# mbed_6LoWPAN_Border_Router_HAT.net
KiCad netlist of a schematic drawn in EAGLE
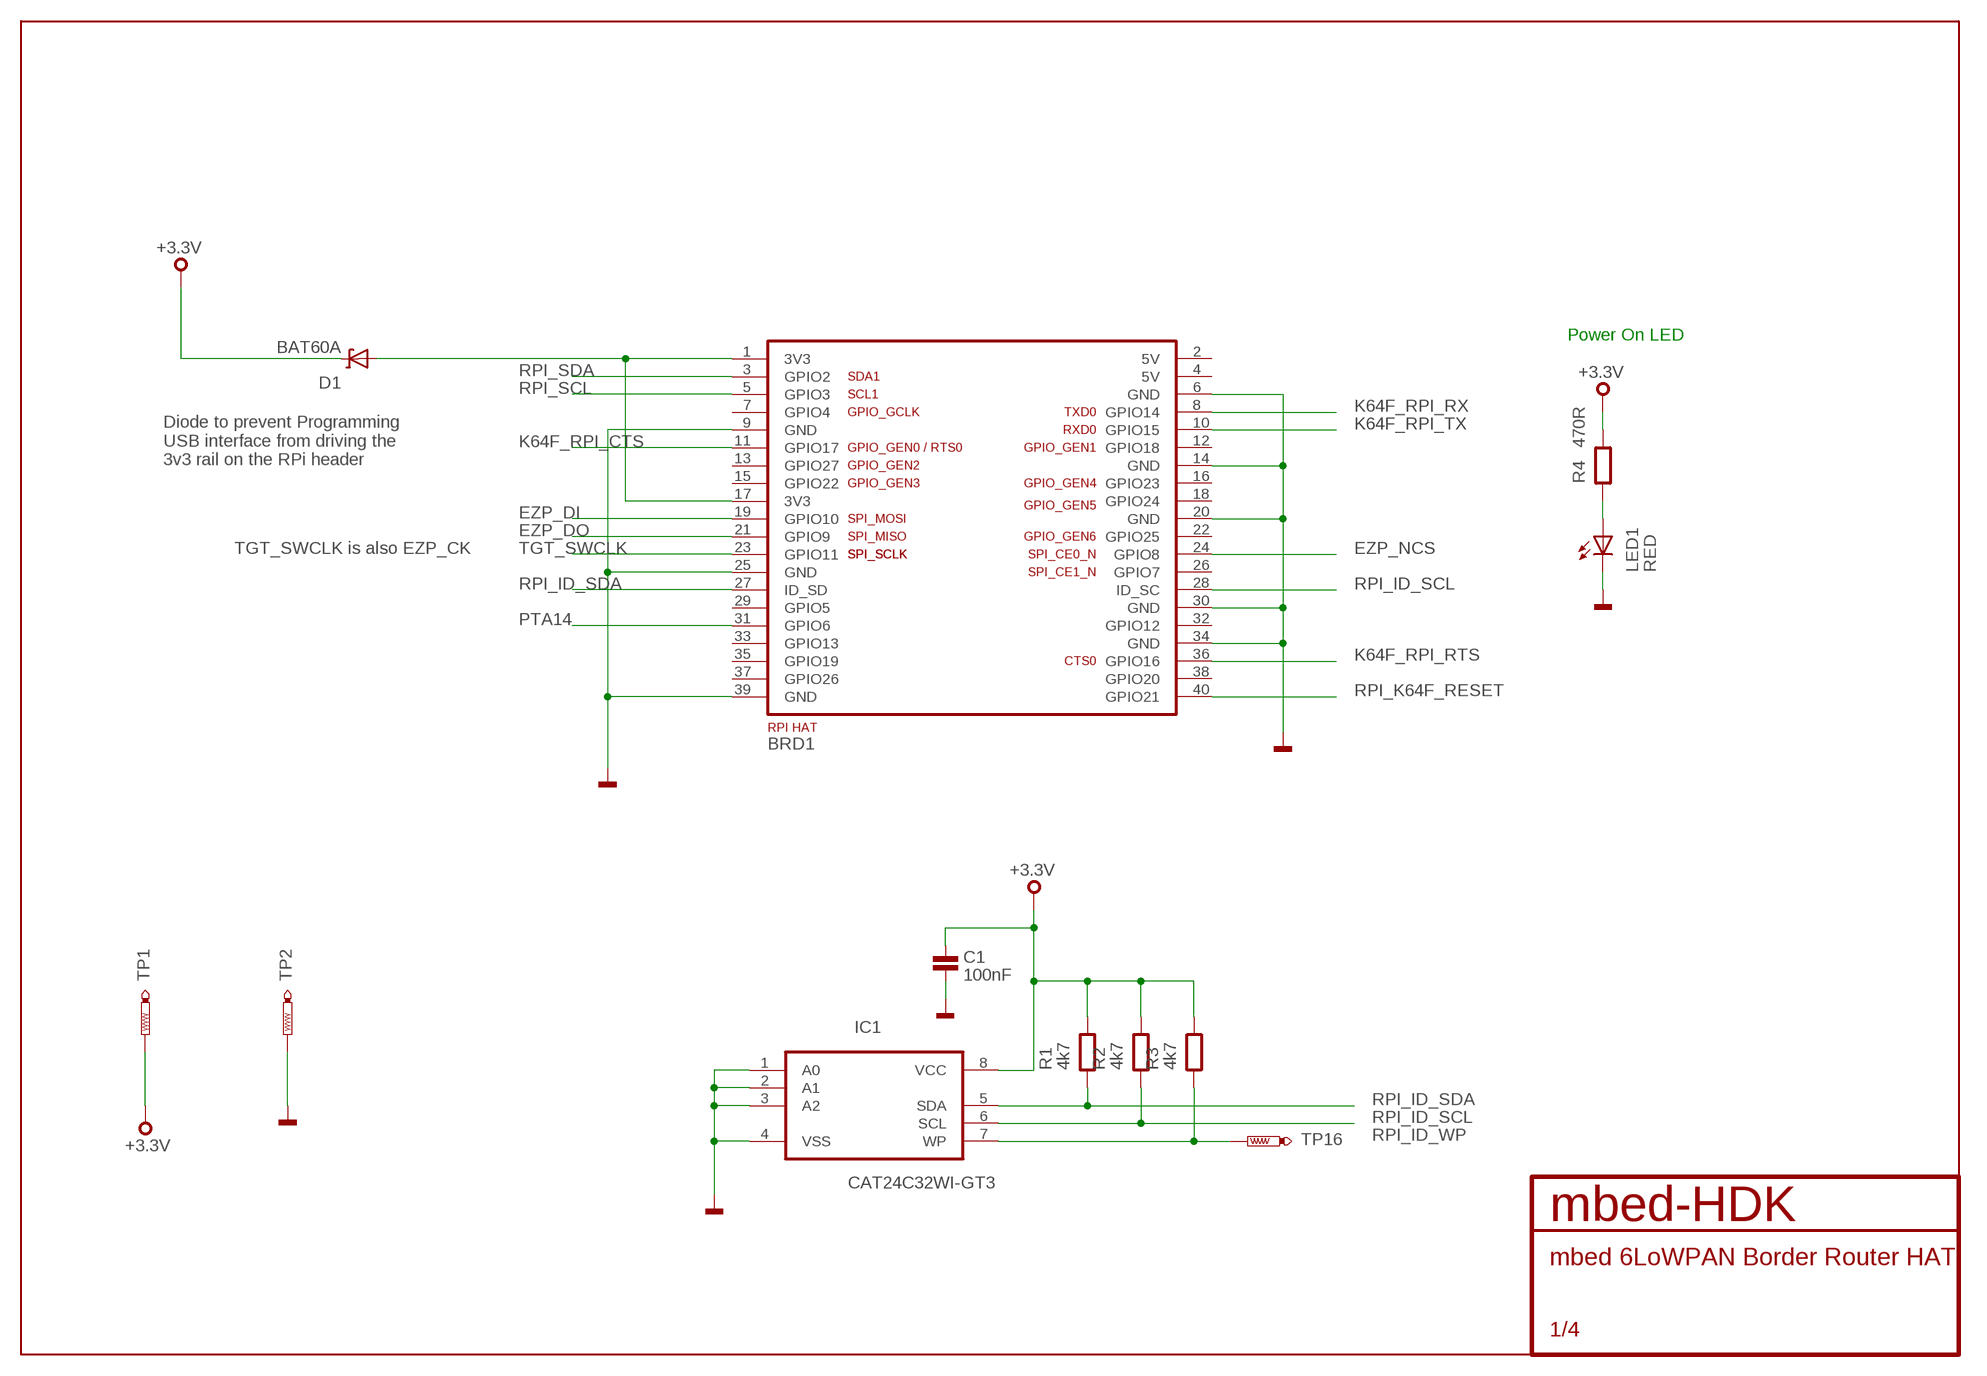
[diagram p0: schematic, sheet 1]
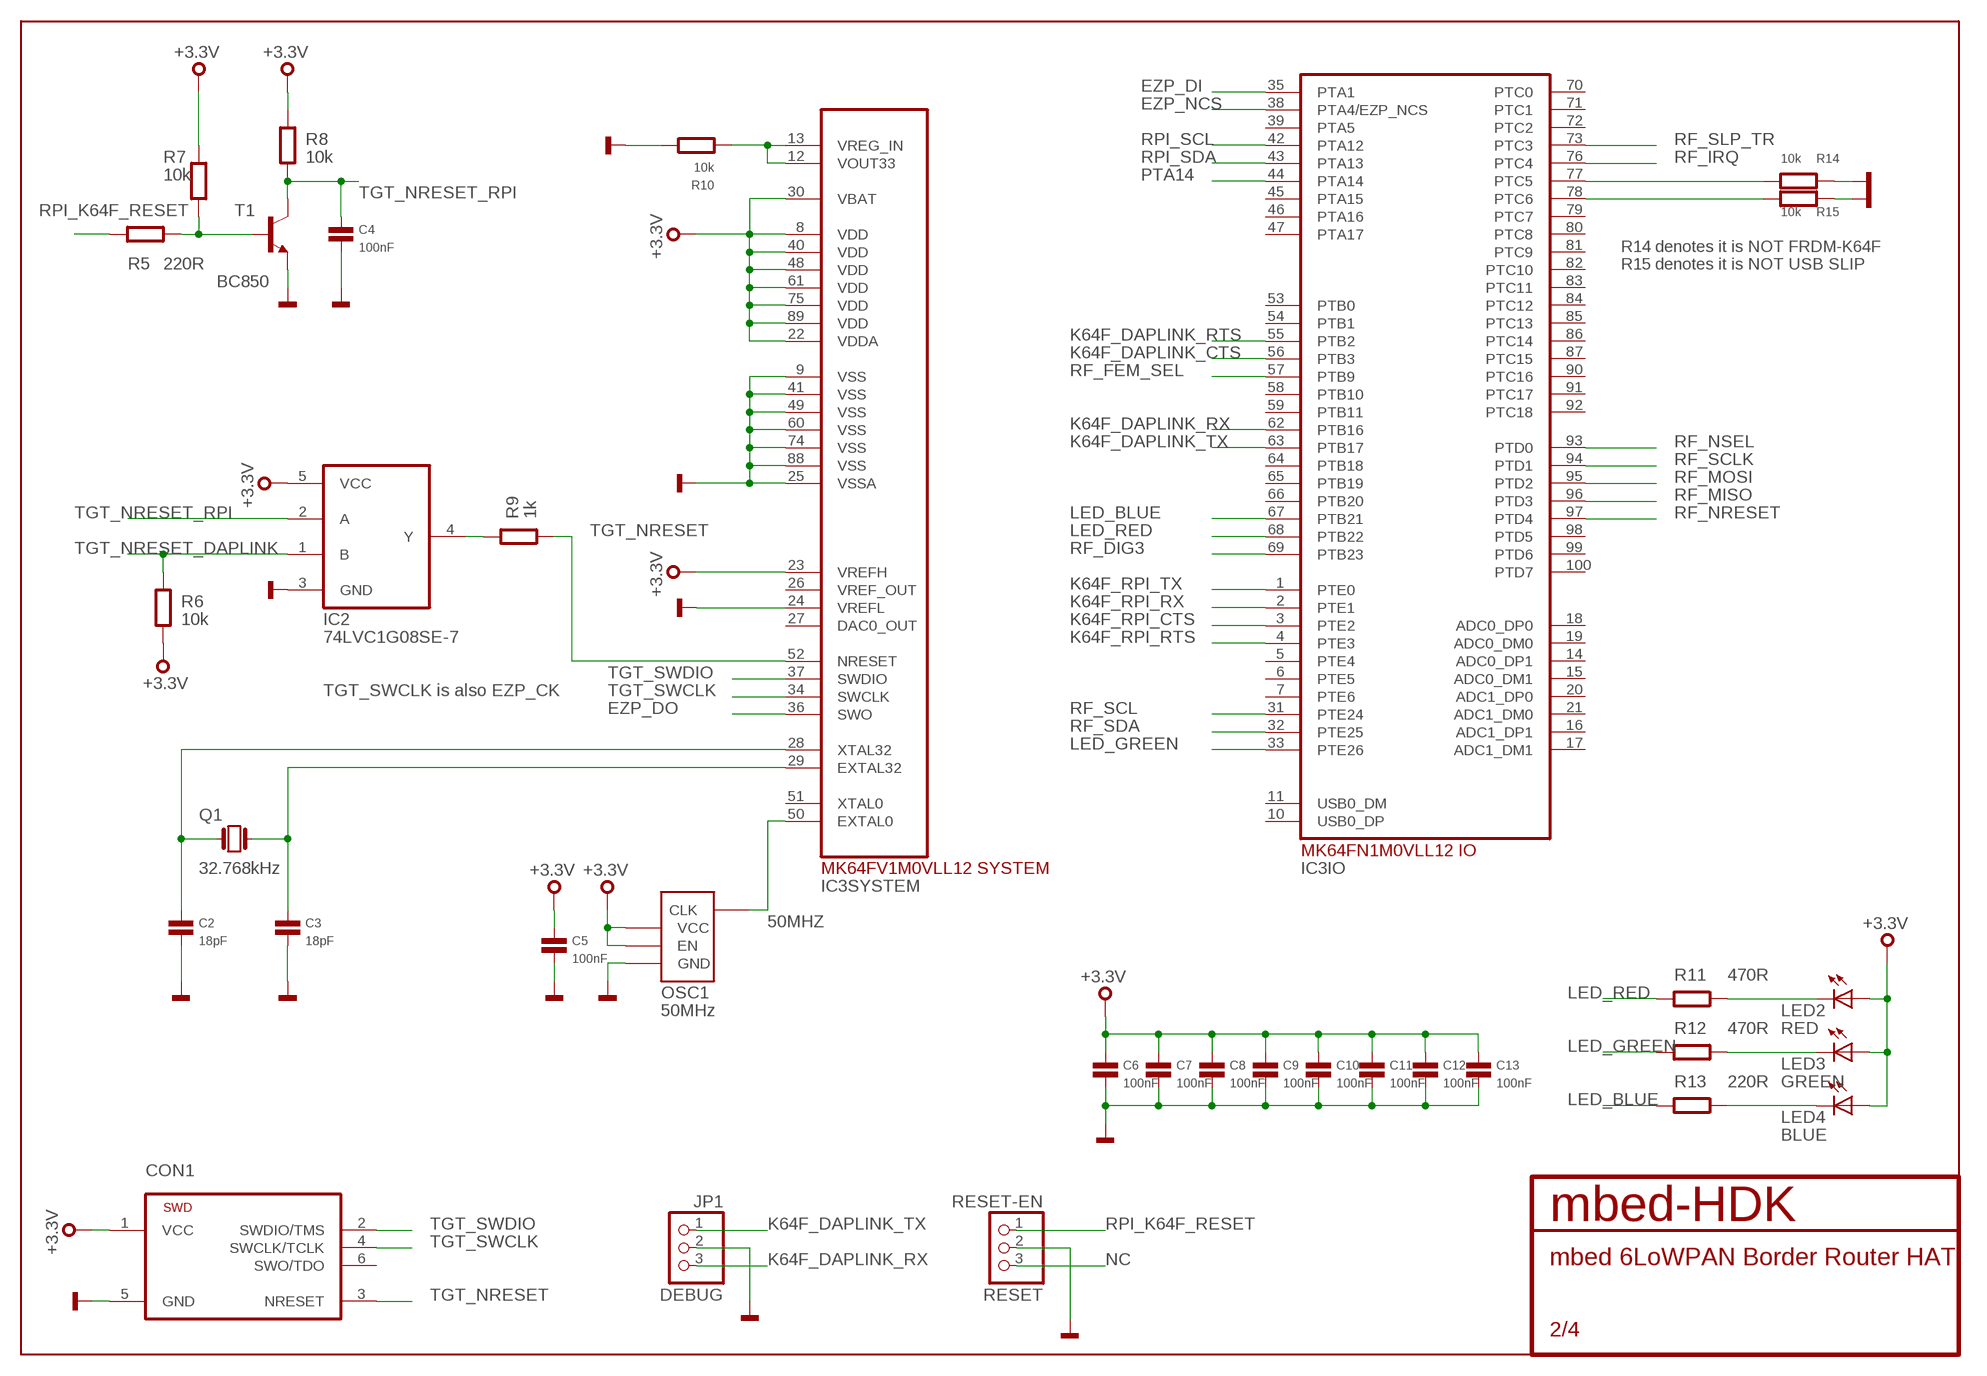
[diagram p1: schematic, sheet 2]
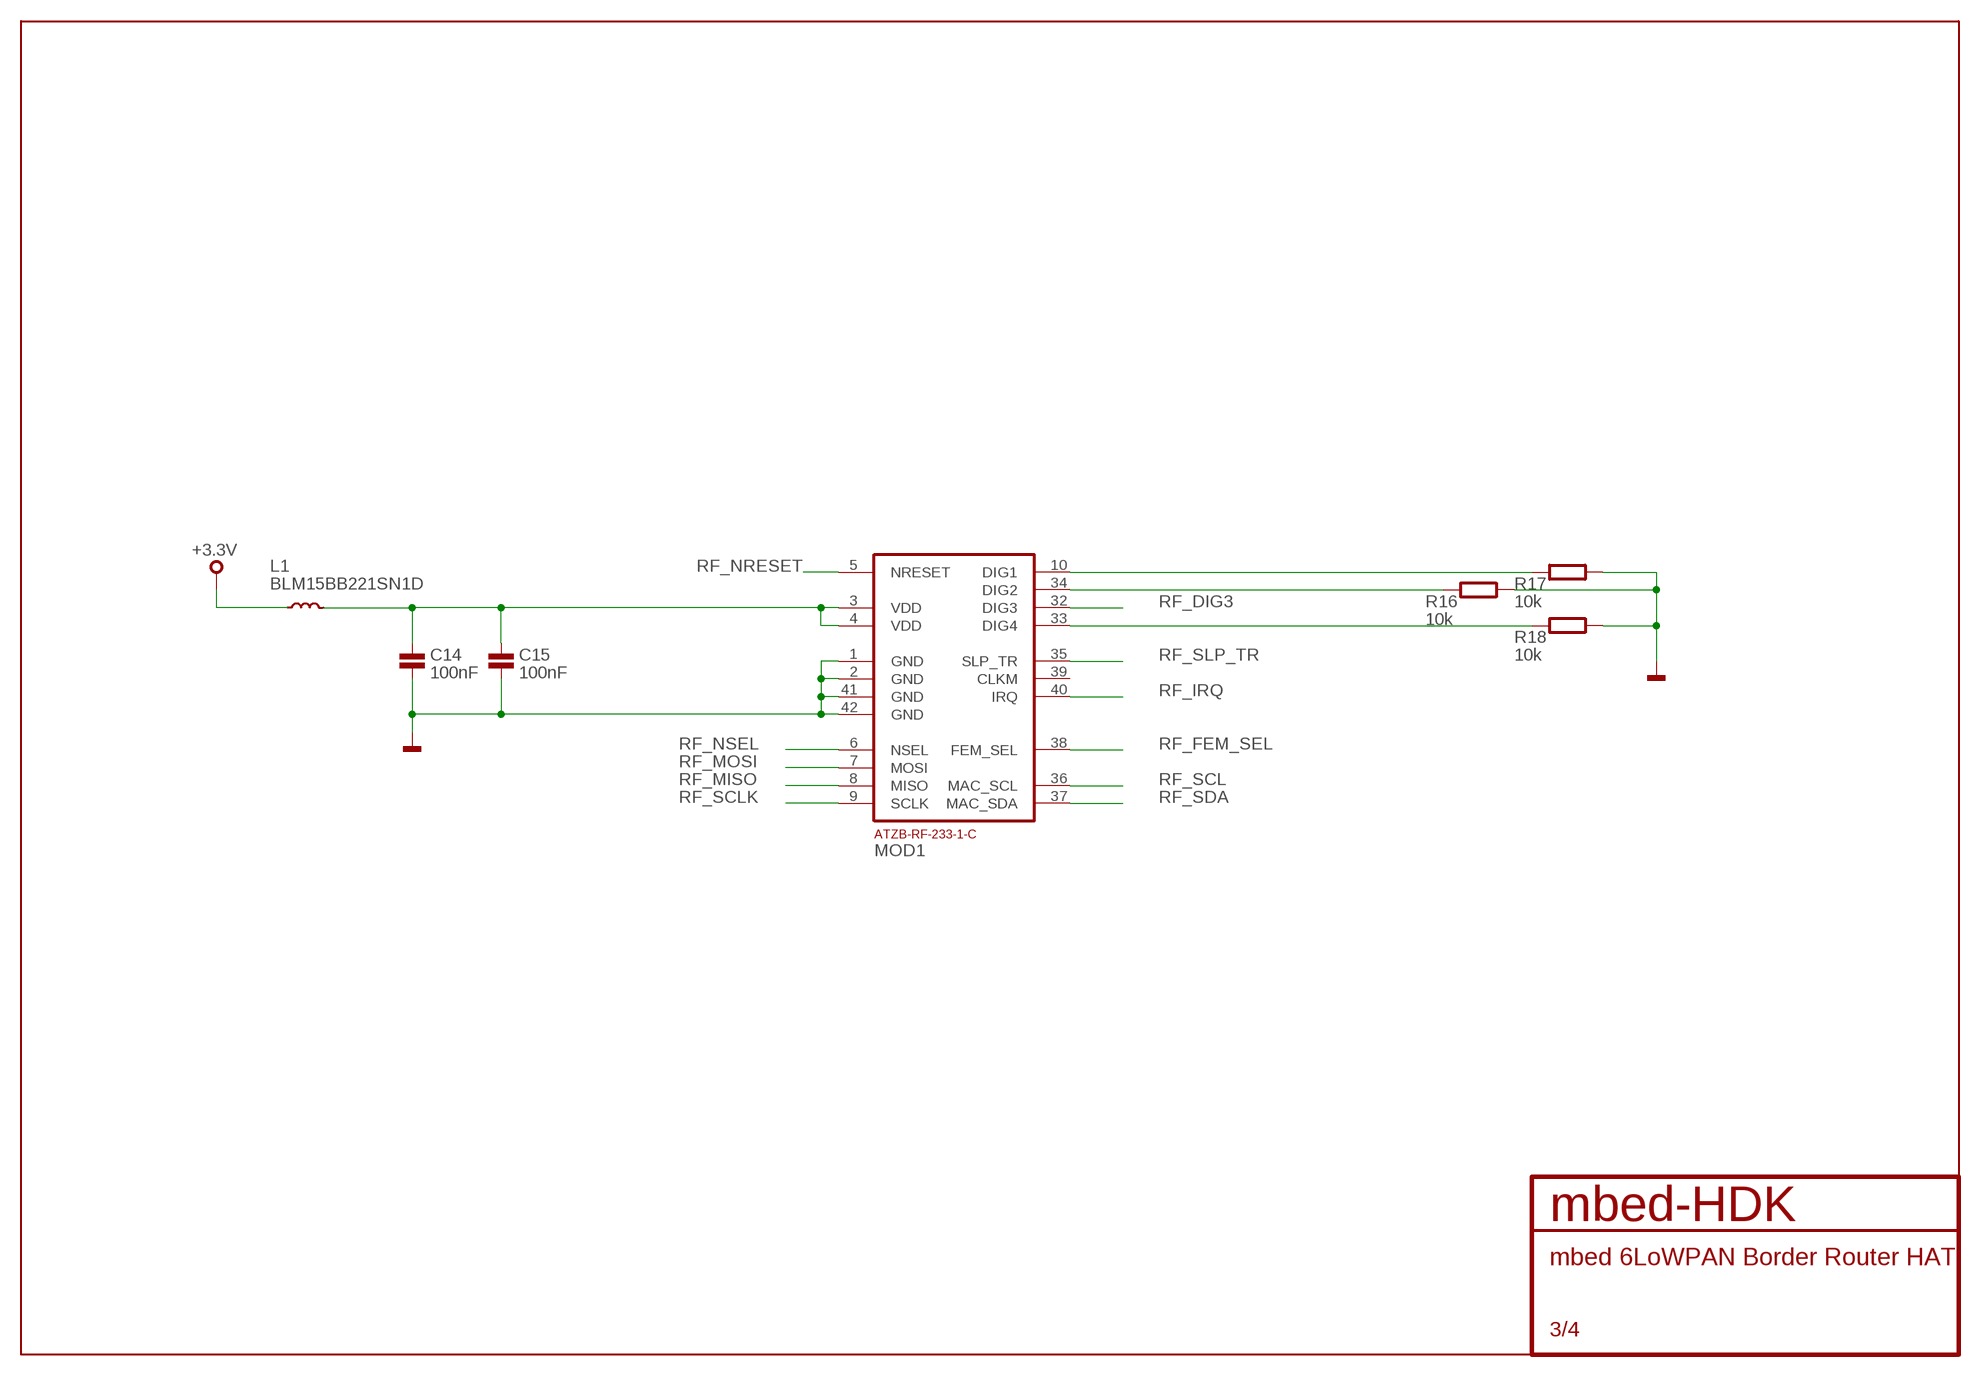
[diagram p2: schematic, sheet 3]
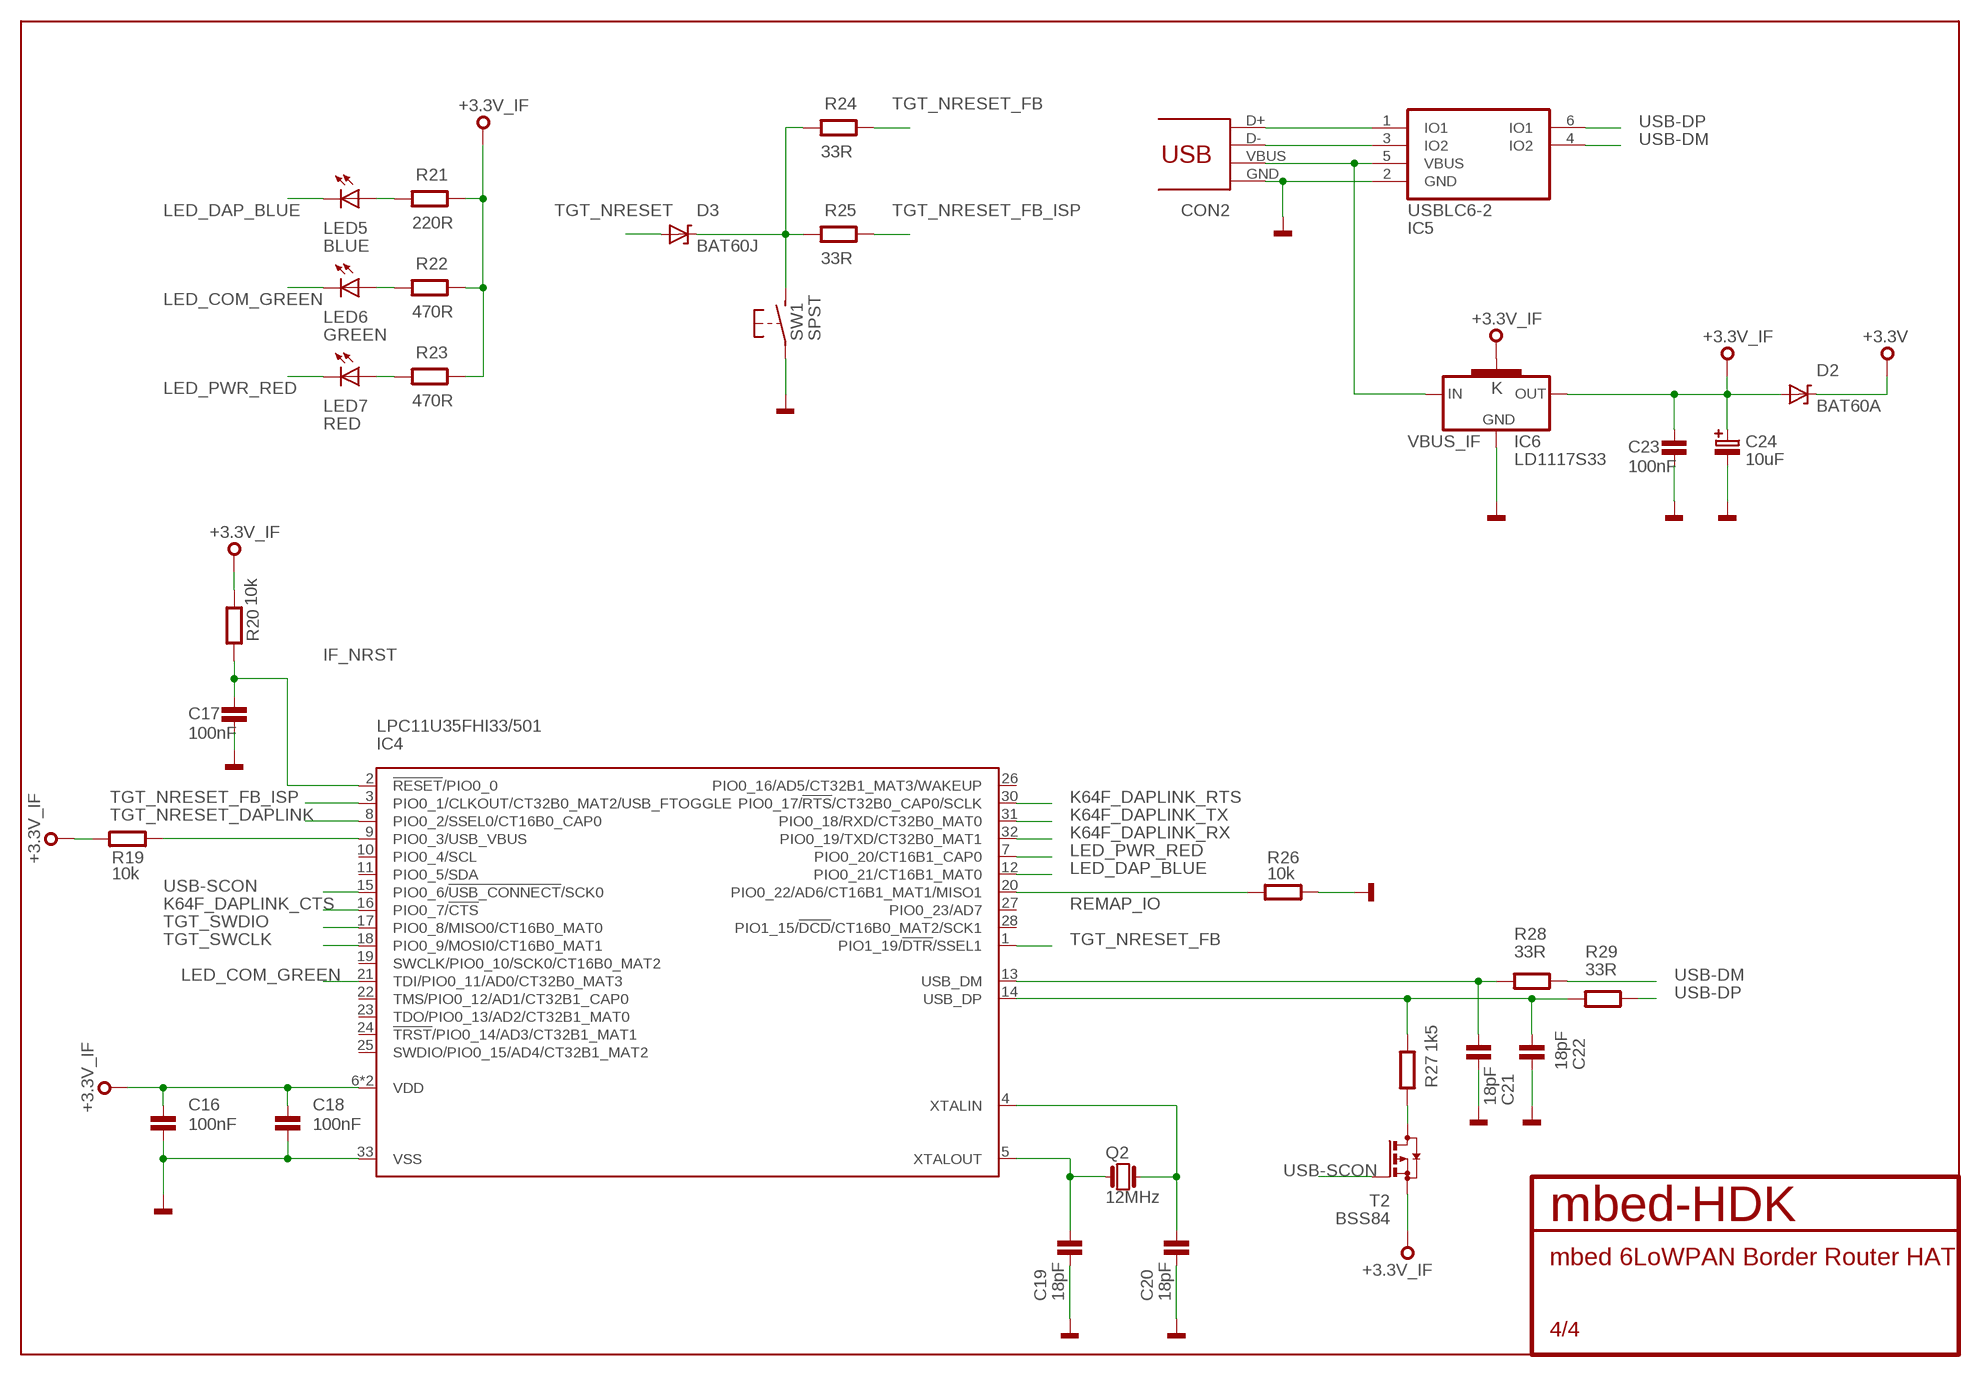
[diagram p3: schematic, sheet 4]

(export (version "E")
  (design (tool "Eeschema 10.0.6"))
  (components
    (comp (ref "C2")
      (value "18pF")
      (footprint "eagle-import:0402")
      (libsource (lib "eagle-import") (part "C0402"))
    )
    (comp (ref "C3")
      (value "18pF")
      (footprint "eagle-import:0402")
      (libsource (lib "eagle-import") (part "C0402"))
    )
    (comp (ref "C4")
      (value "100nF")
      (footprint "eagle-import:0402")
      (libsource (lib "eagle-import") (part "C0402"))
    )
    (comp (ref "C5")
      (value "100nF")
      (footprint "eagle-import:0402")
      (libsource (lib "eagle-import") (part "C0402"))
    )
    (comp (ref "C6")
      (value "100nF")
      (footprint "eagle-import:0402")
      (libsource (lib "eagle-import") (part "C0402"))
    )
    (comp (ref "C7")
      (value "100nF")
      (footprint "eagle-import:0402")
      (libsource (lib "eagle-import") (part "C0402"))
    )
    (comp (ref "C8")
      (value "100nF")
      (footprint "eagle-import:0402")
      (libsource (lib "eagle-import") (part "C0402"))
    )
    (comp (ref "C9")
      (value "100nF")
      (footprint "eagle-import:0402")
      (libsource (lib "eagle-import") (part "C0402"))
    )
    (comp (ref "C10")
      (value "100nF")
      (footprint "eagle-import:0402")
      (libsource (lib "eagle-import") (part "C0402"))
    )
    (comp (ref "C11")
      (value "100nF")
      (footprint "eagle-import:0402")
      (libsource (lib "eagle-import") (part "C0402"))
    )
    (comp (ref "C12")
      (value "100nF")
      (footprint "eagle-import:0402")
      (libsource (lib "eagle-import") (part "C0402"))
    )
    (comp (ref "C13")
      (value "100nF")
      (footprint "eagle-import:0402")
      (libsource (lib "eagle-import") (part "C0402"))
    )
    (comp (ref "CON1")
      (value "TC2030-CTX-NL")
      (footprint "eagle-import:TC2030-CTX-NL")
      (libsource (lib "eagle-import") (part "TC2030-CTX-NL"))
    )
    (comp (ref "IC2")
      (value "74LVC1G08SE-7")
      (footprint "eagle-import:SOT353")
      (libsource (lib "eagle-import") (part "74LVC1GXX"))
    )
    (comp (ref "IC3")
      (value "MK64FN1M0VLL12")
      (footprint "eagle-import:LQFP100")
      (libsource (lib "eagle-import") (part "MK64FN1M0VLL12"))
    )
    (comp (ref "JP1")
      (value "DEBUG")
      (footprint "eagle-import:1X03")
      (libsource (lib "eagle-import") (part "PINHD-1X3"))
    )
    (comp (ref "LED2")
      (value "RED")
      (footprint "eagle-import:CHIPLED_0603")
      (libsource (lib "eagle-import") (part "LED0603"))
    )
    (comp (ref "LED3")
      (value "GREEN")
      (footprint "eagle-import:CHIPLED_0603")
      (libsource (lib "eagle-import") (part "LED0603"))
    )
    (comp (ref "LED4")
      (value "BLUE")
      (footprint "eagle-import:CHIPLED_0603")
      (libsource (lib "eagle-import") (part "LED0603"))
    )
    (comp (ref "OSC1")
      (value "50MHz")
      (footprint "eagle-import:3.2X.2.5")
      (libsource (lib "eagle-import") (part "OSCILLATOR3.2X2.5"))
    )
    (comp (ref "Q1")
      (value "32.768kHz")
      (footprint "eagle-import:FC135")
      (libsource (lib "eagle-import") (part "Q_FC135"))
    )
    (comp (ref "R5")
      (value "220R")
      (footprint "eagle-import:0402")
      (libsource (lib "eagle-import") (part "R0402"))
    )
    (comp (ref "R6")
      (value "10k")
      (footprint "eagle-import:0402")
      (libsource (lib "eagle-import") (part "R0402"))
    )
    (comp (ref "R7")
      (value "10k")
      (footprint "eagle-import:0402")
      (libsource (lib "eagle-import") (part "R0402"))
    )
    (comp (ref "R8")
      (value "10k")
      (footprint "eagle-import:0402")
      (libsource (lib "eagle-import") (part "R0402"))
    )
    (comp (ref "R9")
      (value "1k")
      (footprint "eagle-import:0402")
      (libsource (lib "eagle-import") (part "R0402"))
    )
    (comp (ref "R10")
      (value "10k")
      (footprint "eagle-import:0402")
      (libsource (lib "eagle-import") (part "R0402"))
    )
    (comp (ref "R11")
      (value "470R")
      (footprint "eagle-import:0402")
      (libsource (lib "eagle-import") (part "R0402"))
    )
    (comp (ref "R12")
      (value "470R")
      (footprint "eagle-import:0402")
      (libsource (lib "eagle-import") (part "R0402"))
    )
    (comp (ref "R13")
      (value "220R")
      (footprint "eagle-import:0402")
      (libsource (lib "eagle-import") (part "R0402"))
    )
    (comp (ref "R14")
      (value "10k")
      (footprint "eagle-import:0402")
      (libsource (lib "eagle-import") (part "R0402"))
    )
    (comp (ref "R15")
      (value "10k")
      (footprint "eagle-import:0402")
      (libsource (lib "eagle-import") (part "R0402"))
    )
    (comp (ref "RESET-EN")
      (value "RESET")
      (footprint "eagle-import:1X03")
      (libsource (lib "eagle-import") (part "PINHD-1X3"))
    )
    (comp (ref "T1")
      (value "BC850")
      (footprint "eagle-import:SOT23")
      (libsource (lib "eagle-import") (part "BC850"))
    )
    (comp (ref "BRD1")
      (value "RPI-HAT")
      (footprint "eagle-import:RPI-HAT")
      (libsource (lib "eagle-import") (part "RPI-HAT"))
    )
    (comp (ref "C1")
      (value "100nF")
      (footprint "eagle-import:0402")
      (libsource (lib "eagle-import") (part "C0402"))
    )
    (comp (ref "D1")
      (value "BAT60A")
      (footprint "eagle-import:BAT60A")
      (libsource (lib "eagle-import") (part "BAT60A"))
    )
    (comp (ref "IC1")
      (value "CAT24C32WI-GT3")
      (footprint "eagle-import:SOIC127P600X175-8N")
      (libsource (lib "eagle-import") (part "CAT24C32WI-GT3"))
    )
    (comp (ref "LED1")
      (value "RED")
      (footprint "eagle-import:CHIPLED_0603")
      (libsource (lib "eagle-import") (part "LED0603"))
    )
    (comp (ref "R1")
      (value "4k7")
      (footprint "eagle-import:0402")
      (libsource (lib "eagle-import") (part "R0402"))
    )
    (comp (ref "R2")
      (value "4k7")
      (footprint "eagle-import:0402")
      (libsource (lib "eagle-import") (part "R0402"))
    )
    (comp (ref "R3")
      (value "4k7")
      (footprint "eagle-import:0402")
      (libsource (lib "eagle-import") (part "R0402"))
    )
    (comp (ref "R4")
      (value "470R")
      (footprint "eagle-import:0402")
      (libsource (lib "eagle-import") (part "R0402"))
    )
    (comp (ref "TP1")
      (value "TEST-POINT-50R-PTH")
      (footprint "eagle-import:TP50-PTH")
      (libsource (lib "eagle-import") (part "TEST-POINT-50R-PTH"))
    )
    (comp (ref "TP2")
      (value "TEST-POINT-50R-PTH")
      (footprint "eagle-import:TP50-PTH")
      (libsource (lib "eagle-import") (part "TEST-POINT-50R-PTH"))
    )
    (comp (ref "TP16")
      (value "TEST-POINT-50R-PTH")
      (footprint "eagle-import:TP50-PTH")
      (libsource (lib "eagle-import") (part "TEST-POINT-50R-PTH"))
    )
    (comp (ref "C14")
      (value "100nF")
      (footprint "eagle-import:0402")
      (libsource (lib "eagle-import") (part "C0402"))
    )
    (comp (ref "C15")
      (value "100nF")
      (footprint "eagle-import:0402")
      (libsource (lib "eagle-import") (part "C0402"))
    )
    (comp (ref "L1")
      (value "BLM15BB221SN1D")
      (footprint "eagle-import:0402")
      (libsource (lib "eagle-import") (part "L0402"))
    )
    (comp (ref "MOD1")
      (value "ATZB-RF-233-1-C")
      (footprint "eagle-import:ATZB-RF-233-1-C")
      (libsource (lib "eagle-import") (part "ATZB-RF-233-1-C"))
    )
    (comp (ref "R16")
      (value "10k")
      (footprint "eagle-import:0402")
      (libsource (lib "eagle-import") (part "R0402"))
    )
    (comp (ref "R17")
      (value "10k")
      (footprint "eagle-import:0402")
      (libsource (lib "eagle-import") (part "R0402"))
    )
    (comp (ref "R18")
      (value "10k")
      (footprint "eagle-import:0402")
      (libsource (lib "eagle-import") (part "R0402"))
    )
    (comp (ref "C16")
      (value "100nF")
      (footprint "eagle-import:0402")
      (libsource (lib "eagle-import") (part "C0402"))
    )
    (comp (ref "C17")
      (value "100nF")
      (footprint "eagle-import:0402")
      (libsource (lib "eagle-import") (part "C0402"))
    )
    (comp (ref "C18")
      (value "100nF")
      (footprint "eagle-import:0402")
      (libsource (lib "eagle-import") (part "C0402"))
    )
    (comp (ref "C19")
      (value "18pF")
      (footprint "eagle-import:0402")
      (libsource (lib "eagle-import") (part "C0402"))
    )
    (comp (ref "C20")
      (value "18pF")
      (footprint "eagle-import:0402")
      (libsource (lib "eagle-import") (part "C0402"))
    )
    (comp (ref "C21")
      (value "18pF")
      (footprint "eagle-import:0402")
      (libsource (lib "eagle-import") (part "C0402"))
    )
    (comp (ref "C22")
      (value "18pF")
      (footprint "eagle-import:0402")
      (libsource (lib "eagle-import") (part "C0402"))
    )
    (comp (ref "C23")
      (value "100nF")
      (footprint "eagle-import:0402")
      (libsource (lib "eagle-import") (part "C0402"))
    )
    (comp (ref "C24")
      (value "10uF")
      (footprint "eagle-import:SMC_B")
      (libsource (lib "eagle-import") (part "C-POLB"))
    )
    (comp (ref "CON2")
      (value "USB_MICROB")
      (footprint "eagle-import:MOLEX-47364-0001")
      (libsource (lib "eagle-import") (part "USB_MICROB"))
    )
    (comp (ref "D2")
      (value "BAT60A")
      (footprint "eagle-import:BAT60A")
      (libsource (lib "eagle-import") (part "BAT60A"))
    )
    (comp (ref "D3")
      (value "BAT60J")
      (footprint "eagle-import:BAT60A")
      (libsource (lib "eagle-import") (part "BAT60A"))
    )
    (comp (ref "IC4")
      (value "LPC11U35FHI33/501")
      (footprint "eagle-import:SOT617-3")
      (libsource (lib "eagle-import") (part "LPC11U35FHI33/501"))
    )
    (comp (ref "IC5")
      (value "USBLC6-2SC6")
      (footprint "eagle-import:SOT23-6L")
      (libsource (lib "eagle-import") (part "USBLC6-2SC6"))
    )
    (comp (ref "IC6")
      (value "LD1117S33")
      (footprint "eagle-import:SOT223")
      (libsource (lib "eagle-import") (part "LD1117S33"))
    )
    (comp (ref "LED5")
      (value "BLUE")
      (footprint "eagle-import:CHIPLED_0603")
      (libsource (lib "eagle-import") (part "LED0603"))
    )
    (comp (ref "LED6")
      (value "GREEN")
      (footprint "eagle-import:CHIPLED_0603")
      (libsource (lib "eagle-import") (part "LED0603"))
    )
    (comp (ref "LED7")
      (value "RED")
      (footprint "eagle-import:CHIPLED_0603")
      (libsource (lib "eagle-import") (part "LED0603"))
    )
    (comp (ref "Q2")
      (value "12MHz")
      (footprint "eagle-import:3.2X.2.5")
      (libsource (lib "eagle-import") (part "Q_3.2X2.5"))
    )
    (comp (ref "R19")
      (value "10k")
      (footprint "eagle-import:0402")
      (libsource (lib "eagle-import") (part "R0402"))
    )
    (comp (ref "R20")
      (value "10k")
      (footprint "eagle-import:0402")
      (libsource (lib "eagle-import") (part "R0402"))
    )
    (comp (ref "R21")
      (value "220R")
      (footprint "eagle-import:0402")
      (libsource (lib "eagle-import") (part "R0402"))
    )
    (comp (ref "R22")
      (value "470R")
      (footprint "eagle-import:0402")
      (libsource (lib "eagle-import") (part "R0402"))
    )
    (comp (ref "R23")
      (value "470R")
      (footprint "eagle-import:0402")
      (libsource (lib "eagle-import") (part "R0402"))
    )
    (comp (ref "R24")
      (value "33R")
      (footprint "eagle-import:0402")
      (libsource (lib "eagle-import") (part "R0402"))
    )
    (comp (ref "R25")
      (value "33R")
      (footprint "eagle-import:0402")
      (libsource (lib "eagle-import") (part "R0402"))
    )
    (comp (ref "R26")
      (value "10k")
      (footprint "eagle-import:0402")
      (libsource (lib "eagle-import") (part "R0402"))
    )
    (comp (ref "R27")
      (value "1k5")
      (footprint "eagle-import:0402")
      (libsource (lib "eagle-import") (part "R0402"))
    )
    (comp (ref "R28")
      (value "33R")
      (footprint "eagle-import:0402")
      (libsource (lib "eagle-import") (part "R0402"))
    )
    (comp (ref "R29")
      (value "33R")
      (footprint "eagle-import:0402")
      (libsource (lib "eagle-import") (part "R0402"))
    )
    (comp (ref "SW1")
      (value "SPST")
      (footprint "eagle-import:DTSM-32S-B")
      (libsource (lib "eagle-import") (part "SPST"))
    )
    (comp (ref "T2")
      (value "BSS84")
      (footprint "eagle-import:SOT23")
      (libsource (lib "eagle-import") (part "BSS84"))
    )
  )
  (nets
    (net (code "1") (name "+3.3V") (class "Default")
      (node (ref "C1") (pin "1") (pinfunction "P$1_1") (pintype "passive"))
      (node (ref "C10") (pin "1") (pinfunction "P$1_1") (pintype "passive"))
      (node (ref "C11") (pin "1") (pinfunction "P$1_1") (pintype "passive"))
      (node (ref "C12") (pin "1") (pinfunction "P$1_1") (pintype "passive"))
      (node (ref "C13") (pin "1") (pinfunction "P$1_1") (pintype "passive"))
      (node (ref "C5") (pin "1") (pinfunction "P$1_1") (pintype "passive"))
      (node (ref "C6") (pin "1") (pinfunction "P$1_1") (pintype "passive"))
      (node (ref "C7") (pin "1") (pinfunction "P$1_1") (pintype "passive"))
      (node (ref "C8") (pin "1") (pinfunction "P$1_1") (pintype "passive"))
      (node (ref "C9") (pin "1") (pinfunction "P$1_1") (pintype "passive"))
      (node (ref "CON1") (pin "1") (pinfunction "VCC_1") (pintype "passive"))
      (node (ref "D1") (pin "K") (pinfunction "K_K") (pintype "passive"))
      (node (ref "D2") (pin "K") (pinfunction "K_K") (pintype "passive"))
      (node (ref "IC1") (pin "8") (pinfunction "VCC_8") (pintype "passive"))
      (node (ref "IC2") (pin "5") (pinfunction "VCC_5") (pintype "bidirectional"))
      (node (ref "IC3") (pin "22") (pinfunction "VDDA_22") (pintype "bidirectional"))
      (node (ref "IC3") (pin "23") (pinfunction "VREFH_23") (pintype "bidirectional"))
      (node (ref "IC3") (pin "30") (pinfunction "VBAT_30") (pintype "bidirectional"))
      (node (ref "IC3") (pin "40") (pinfunction "VDD_40") (pintype "bidirectional"))
      (node (ref "IC3") (pin "48") (pinfunction "VDD_48") (pintype "bidirectional"))
      (node (ref "IC3") (pin "61") (pinfunction "VDD_61") (pintype "bidirectional"))
      (node (ref "IC3") (pin "75") (pinfunction "VDD_75") (pintype "bidirectional"))
      (node (ref "IC3") (pin "8") (pinfunction "VDD_8") (pintype "bidirectional"))
      (node (ref "IC3") (pin "89") (pinfunction "VDD_89") (pintype "bidirectional"))
      (node (ref "L1") (pin "1") (pinfunction "P$1_1") (pintype "bidirectional"))
      (node (ref "LED2") (pin "A") (pinfunction "A_A") (pintype "passive"))
      (node (ref "LED3") (pin "A") (pinfunction "A_A") (pintype "passive"))
      (node (ref "LED4") (pin "A") (pinfunction "A_A") (pintype "passive"))
      (node (ref "OSC1") (pin "P$1") (pinfunction "EN_P$1") (pintype "bidirectional"))
      (node (ref "OSC1") (pin "P$4") (pinfunction "VCC_P$4") (pintype "bidirectional"))
      (node (ref "R1") (pin "2") (pinfunction "P$2_2") (pintype "passive"))
      (node (ref "R2") (pin "2") (pinfunction "P$2_2") (pintype "passive"))
      (node (ref "R3") (pin "2") (pinfunction "P$2_2") (pintype "passive"))
      (node (ref "R4") (pin "2") (pinfunction "P$2_2") (pintype "passive"))
      (node (ref "R6") (pin "1") (pinfunction "P$1_1") (pintype "passive"))
      (node (ref "R7") (pin "1") (pinfunction "P$1_1") (pintype "passive"))
      (node (ref "R8") (pin "2") (pinfunction "P$2_2") (pintype "passive"))
      (node (ref "TP1") (pin "TP") (pinfunction "TP_TP") (pintype "input"))
    )
    (net (code "2") (name "+3.3V_IF") (class "Default")
      (node (ref "C16") (pin "1") (pinfunction "P$1_1") (pintype "passive"))
      (node (ref "C18") (pin "1") (pinfunction "P$1_1") (pintype "passive"))
      (node (ref "C23") (pin "1") (pinfunction "P$1_1") (pintype "passive"))
      (node (ref "C24") (pin "+") (pinfunction "+_+") (pintype "passive"))
      (node (ref "D2") (pin "A") (pinfunction "A_A") (pintype "passive"))
      (node (ref "IC4") (pin "29") (pinfunction "VDD_29") (pintype "passive"))
      (node (ref "IC4") (pin "6") (pinfunction "VDD_6") (pintype "passive"))
      (node (ref "IC6") (pin "2") (pinfunction "OUT_2") (pintype "passive"))
      (node (ref "IC6") (pin "4") (pinfunction "K_4") (pintype "passive"))
      (node (ref "R19") (pin "2") (pinfunction "P$2_2") (pintype "passive"))
      (node (ref "R20") (pin "2") (pinfunction "P$2_2") (pintype "passive"))
      (node (ref "R21") (pin "1") (pinfunction "P$1_1") (pintype "passive"))
      (node (ref "R22") (pin "1") (pinfunction "P$1_1") (pintype "passive"))
      (node (ref "R23") (pin "1") (pinfunction "P$1_1") (pintype "passive"))
      (node (ref "T2") (pin "2") (pinfunction "S_2") (pintype "passive"))
    )
    (net (code "3") (name "50MHZ") (class "Default")
      (node (ref "IC3") (pin "50") (pinfunction "EXTAL0_50") (pintype "bidirectional"))
      (node (ref "OSC1") (pin "P$3") (pinfunction "CLK_P$3") (pintype "bidirectional"))
    )
    (net (code "4") (name "EZP_DI") (class "Default")
      (node (ref "BRD1") (pin "19") (pinfunction "GPIO10_19") (pintype "bidirectional"))
      (node (ref "IC3") (pin "35") (pinfunction "PTA1_35") (pintype "bidirectional"))
    )
    (net (code "5") (name "EZP_DO") (class "Default")
      (node (ref "BRD1") (pin "21") (pinfunction "GPIO9_21") (pintype "bidirectional"))
      (node (ref "IC3") (pin "36") (pinfunction "SWO_36") (pintype "bidirectional"))
    )
    (net (code "6") (name "EZP_NCS") (class "Default")
      (node (ref "BRD1") (pin "24") (pinfunction "GPIO8_24") (pintype "bidirectional"))
      (node (ref "IC3") (pin "38") (pinfunction "PTA4/EZP_NCS_38") (pintype "bidirectional"))
    )
    (net (code "7") (name "GND") (class "Default")
      (node (ref "BRD1") (pin "14") (pinfunction "GND_14") (pintype "bidirectional"))
      (node (ref "BRD1") (pin "20") (pinfunction "GND_20") (pintype "bidirectional"))
      (node (ref "BRD1") (pin "25") (pinfunction "GND_25") (pintype "bidirectional"))
      (node (ref "BRD1") (pin "30") (pinfunction "GND_30") (pintype "bidirectional"))
      (node (ref "BRD1") (pin "34") (pinfunction "GND_34") (pintype "bidirectional"))
      (node (ref "BRD1") (pin "39") (pinfunction "GND_39") (pintype "bidirectional"))
      (node (ref "BRD1") (pin "6") (pinfunction "GND_6") (pintype "bidirectional"))
      (node (ref "BRD1") (pin "9") (pinfunction "GND_9") (pintype "bidirectional"))
      (node (ref "C1") (pin "2") (pinfunction "P$2_2") (pintype "passive"))
      (node (ref "C10") (pin "2") (pinfunction "P$2_2") (pintype "passive"))
      (node (ref "C11") (pin "2") (pinfunction "P$2_2") (pintype "passive"))
      (node (ref "C12") (pin "2") (pinfunction "P$2_2") (pintype "passive"))
      (node (ref "C13") (pin "2") (pinfunction "P$2_2") (pintype "passive"))
      (node (ref "C14") (pin "2") (pinfunction "P$2_2") (pintype "passive"))
      (node (ref "C15") (pin "2") (pinfunction "P$2_2") (pintype "passive"))
      (node (ref "C16") (pin "2") (pinfunction "P$2_2") (pintype "passive"))
      (node (ref "C17") (pin "2") (pinfunction "P$2_2") (pintype "passive"))
      (node (ref "C18") (pin "2") (pinfunction "P$2_2") (pintype "passive"))
      (node (ref "C19") (pin "2") (pinfunction "P$2_2") (pintype "passive"))
      (node (ref "C2") (pin "2") (pinfunction "P$2_2") (pintype "passive"))
      (node (ref "C20") (pin "2") (pinfunction "P$2_2") (pintype "passive"))
      (node (ref "C21") (pin "2") (pinfunction "P$2_2") (pintype "passive"))
      (node (ref "C22") (pin "2") (pinfunction "P$2_2") (pintype "passive"))
      (node (ref "C23") (pin "2") (pinfunction "P$2_2") (pintype "passive"))
      (node (ref "C24") (pin "-") (pinfunction "-_-") (pintype "passive"))
      (node (ref "C3") (pin "2") (pinfunction "P$2_2") (pintype "passive"))
      (node (ref "C4") (pin "2") (pinfunction "P$2_2") (pintype "passive"))
      (node (ref "C5") (pin "2") (pinfunction "P$2_2") (pintype "passive"))
      (node (ref "C6") (pin "2") (pinfunction "P$2_2") (pintype "passive"))
      (node (ref "C7") (pin "2") (pinfunction "P$2_2") (pintype "passive"))
      (node (ref "C8") (pin "2") (pinfunction "P$2_2") (pintype "passive"))
      (node (ref "C9") (pin "2") (pinfunction "P$2_2") (pintype "passive"))
      (node (ref "CON1") (pin "5") (pinfunction "GND_5") (pintype "passive"))
      (node (ref "CON2") (pin "GND") (pinfunction "GND_GND") (pintype "bidirectional"))
      (node (ref "IC1") (pin "1") (pinfunction "A0_1") (pintype "input"))
      (node (ref "IC1") (pin "2") (pinfunction "A1_2") (pintype "input"))
      (node (ref "IC1") (pin "3") (pinfunction "A2_3") (pintype "input"))
      (node (ref "IC1") (pin "4") (pinfunction "VSS_4") (pintype "passive"))
      (node (ref "IC2") (pin "3") (pinfunction "GND_3") (pintype "bidirectional"))
      (node (ref "IC3") (pin "24") (pinfunction "VREFL_24") (pintype "bidirectional"))
      (node (ref "IC3") (pin "25") (pinfunction "VSSA_25") (pintype "bidirectional"))
      (node (ref "IC3") (pin "41") (pinfunction "VSS_41") (pintype "bidirectional"))
      (node (ref "IC3") (pin "49") (pinfunction "VSS_49") (pintype "bidirectional"))
      (node (ref "IC3") (pin "60") (pinfunction "VSS_60") (pintype "bidirectional"))
      (node (ref "IC3") (pin "74") (pinfunction "VSS_74") (pintype "bidirectional"))
      (node (ref "IC3") (pin "88") (pinfunction "VSS_88") (pintype "bidirectional"))
      (node (ref "IC3") (pin "9") (pinfunction "VSS_9") (pintype "bidirectional"))
      (node (ref "IC4") (pin "33") (pinfunction "VSS_33") (pintype "passive"))
      (node (ref "IC5") (pin "2") (pinfunction "GND_2") (pintype "bidirectional"))
      (node (ref "IC6") (pin "1") (pinfunction "GND_1") (pintype "input"))
      (node (ref "JP1") (pin "2") (pinfunction "2_2") (pintype "passive"))
      (node (ref "LED1") (pin "C") (pinfunction "C_C") (pintype "passive"))
      (node (ref "MOD1") (pin "1") (pinfunction "GND_1") (pintype "bidirectional"))
      (node (ref "MOD1") (pin "2") (pinfunction "GND_2") (pintype "bidirectional"))
      (node (ref "MOD1") (pin "41") (pinfunction "GND_41") (pintype "bidirectional"))
      (node (ref "MOD1") (pin "42") (pinfunction "GND_42") (pintype "bidirectional"))
      (node (ref "OSC1") (pin "P$2") (pinfunction "GND_P$2") (pintype "bidirectional"))
      (node (ref "R10") (pin "2") (pinfunction "P$2_2") (pintype "passive"))
      (node (ref "R14") (pin "2") (pinfunction "P$2_2") (pintype "passive"))
      (node (ref "R15") (pin "2") (pinfunction "P$2_2") (pintype "passive"))
      (node (ref "R16") (pin "2") (pinfunction "P$2_2") (pintype "passive"))
      (node (ref "R17") (pin "2") (pinfunction "P$2_2") (pintype "passive"))
      (node (ref "R18") (pin "1") (pinfunction "P$1_1") (pintype "passive"))
      (node (ref "R26") (pin "1") (pinfunction "P$1_1") (pintype "passive"))
      (node (ref "RESET-EN") (pin "2") (pinfunction "2_2") (pintype "passive"))
      (node (ref "SW1") (pin "P$1") (pinfunction "P_P$1") (pintype "passive"))
      (node (ref "T1") (pin "2") (pinfunction "E_2") (pintype "passive"))
      (node (ref "TP2") (pin "TP") (pinfunction "TP_TP") (pintype "input"))
    )
    (net (code "8") (name "IF_NRST") (class "Default")
      (node (ref "C17") (pin "1") (pinfunction "P$1_1") (pintype "passive"))
      (node (ref "IC4") (pin "2") (pinfunction "~{RESET}/PIO0_0_2") (pintype "bidirectional"))
      (node (ref "R20") (pin "1") (pinfunction "P$1_1") (pintype "passive"))
    )
    (net (code "9") (name "K64F_DAPLINK_CTS") (class "Default")
      (node (ref "IC3") (pin "56") (pinfunction "PTB3_56") (pintype "bidirectional"))
      (node (ref "IC4") (pin "16") (pinfunction "PIO0_7/~{CTS}_16") (pintype "bidirectional"))
    )
    (net (code "10") (name "K64F_DAPLINK_RTS") (class "Default")
      (node (ref "IC3") (pin "55") (pinfunction "PTB2_55") (pintype "bidirectional"))
      (node (ref "IC4") (pin "30") (pinfunction "PIO0_17/~{RTS}/CT32B0_CAP0/SCLK_30") (pintype "bidirectional"))
    )
    (net (code "11") (name "K64F_DAPLINK_RX") (class "Default")
      (node (ref "IC3") (pin "62") (pinfunction "PTB16_62") (pintype "bidirectional"))
      (node (ref "IC4") (pin "32") (pinfunction "PIO0_19/TXD/CT32B0_MAT1_32") (pintype "bidirectional"))
      (node (ref "JP1") (pin "3") (pinfunction "3_3") (pintype "passive"))
    )
    (net (code "12") (name "K64F_DAPLINK_TX") (class "Default")
      (node (ref "IC3") (pin "63") (pinfunction "PTB17_63") (pintype "bidirectional"))
      (node (ref "IC4") (pin "31") (pinfunction "PIO0_18/RXD/CT32B0_MAT0_31") (pintype "bidirectional"))
      (node (ref "JP1") (pin "1") (pinfunction "1_1") (pintype "passive"))
    )
    (net (code "13") (name "K64F_RPI_CTS") (class "Default")
      (node (ref "BRD1") (pin "11") (pinfunction "GPIO17_11") (pintype "bidirectional"))
      (node (ref "IC3") (pin "3") (pinfunction "PTE2_3") (pintype "bidirectional"))
    )
    (net (code "14") (name "K64F_RPI_RTS") (class "Default")
      (node (ref "BRD1") (pin "36") (pinfunction "GPIO16_36") (pintype "bidirectional"))
      (node (ref "IC3") (pin "4") (pinfunction "PTE3_4") (pintype "bidirectional"))
    )
    (net (code "15") (name "K64F_RPI_RX") (class "Default")
      (node (ref "BRD1") (pin "8") (pinfunction "GPIO14_8") (pintype "bidirectional"))
      (node (ref "IC3") (pin "2") (pinfunction "PTE1_2") (pintype "bidirectional"))
    )
    (net (code "16") (name "K64F_RPI_TX") (class "Default")
      (node (ref "BRD1") (pin "10") (pinfunction "GPIO15_10") (pintype "bidirectional"))
      (node (ref "IC3") (pin "1") (pinfunction "PTE0_1") (pintype "bidirectional"))
    )
    (net (code "17") (name "LED_BLUE") (class "Default")
      (node (ref "IC3") (pin "67") (pinfunction "PTB21_67") (pintype "bidirectional"))
      (node (ref "R13") (pin "1") (pinfunction "P$1_1") (pintype "passive"))
    )
    (net (code "18") (name "LED_COM_GREEN") (class "Default")
      (node (ref "IC4") (pin "21") (pinfunction "TDI/PIO0_11/AD0/CT32B0_MAT3_21") (pintype "bidirectional"))
      (node (ref "LED6") (pin "C") (pinfunction "C_C") (pintype "passive"))
    )
    (net (code "19") (name "LED_DAP_BLUE") (class "Default")
      (node (ref "IC4") (pin "12") (pinfunction "PIO0_21/CT16B1_MAT0_12") (pintype "bidirectional"))
      (node (ref "LED5") (pin "C") (pinfunction "C_C") (pintype "passive"))
    )
    (net (code "20") (name "LED_GREEN") (class "Default")
      (node (ref "IC3") (pin "33") (pinfunction "PTE26_33") (pintype "bidirectional"))
      (node (ref "R12") (pin "1") (pinfunction "P$1_1") (pintype "passive"))
    )
    (net (code "21") (name "LED_PWR_RED") (class "Default")
      (node (ref "IC4") (pin "7") (pinfunction "PIO0_20/CT16B1_CAP0_7") (pintype "bidirectional"))
      (node (ref "LED7") (pin "C") (pinfunction "C_C") (pintype "passive"))
    )
    (net (code "22") (name "LED_RED") (class "Default")
      (node (ref "IC3") (pin "68") (pinfunction "PTB22_68") (pintype "bidirectional"))
      (node (ref "R11") (pin "1") (pinfunction "P$1_1") (pintype "passive"))
    )
    (net (code "23") (name "NC") (class "Default")
      (node (ref "RESET-EN") (pin "3") (pinfunction "3_3") (pintype "passive"))
    )
    (net (code "24") (name "Net-(BRD1-3V3-Pad1)") (class "Default")
      (node (ref "BRD1") (pin "1") (pinfunction "3V3_1") (pintype "bidirectional"))
      (node (ref "BRD1") (pin "17") (pinfunction "3V3_17") (pintype "bidirectional"))
      (node (ref "D1") (pin "A") (pinfunction "A_A") (pintype "passive"))
    )
    (net (code "25") (name "Net-(C2-P$1)") (class "Default")
      (node (ref "C2") (pin "1") (pinfunction "P$1_1") (pintype "passive"))
      (node (ref "IC3") (pin "28") (pinfunction "XTAL32_28") (pintype "bidirectional"))
      (node (ref "Q1") (pin "X1") (pinfunction "1_X1") (pintype "passive"))
    )
    (net (code "26") (name "Net-(C3-P$1)") (class "Default")
      (node (ref "C3") (pin "1") (pinfunction "P$1_1") (pintype "passive"))
      (node (ref "IC3") (pin "29") (pinfunction "EXTAL32_29") (pintype "bidirectional"))
      (node (ref "Q1") (pin "X2") (pinfunction "2_X2") (pintype "passive"))
    )
    (net (code "27") (name "Net-(C14-P$1)") (class "Default")
      (node (ref "C14") (pin "1") (pinfunction "P$1_1") (pintype "passive"))
      (node (ref "C15") (pin "1") (pinfunction "P$1_1") (pintype "passive"))
      (node (ref "L1") (pin "2") (pinfunction "P$2_2") (pintype "bidirectional"))
      (node (ref "MOD1") (pin "3") (pinfunction "VDD_3") (pintype "bidirectional"))
      (node (ref "MOD1") (pin "4") (pinfunction "VDD_4") (pintype "bidirectional"))
    )
    (net (code "28") (name "Net-(C19-P$1)") (class "Default")
      (node (ref "C19") (pin "1") (pinfunction "P$1_1") (pintype "passive"))
      (node (ref "IC4") (pin "5") (pinfunction "XTALOUT_5") (pintype "output"))
      (node (ref "Q2") (pin "P$1") (pinfunction "1_P$1") (pintype "passive"))
    )
    (net (code "29") (name "Net-(C20-P$1)") (class "Default")
      (node (ref "C20") (pin "1") (pinfunction "P$1_1") (pintype "passive"))
      (node (ref "IC4") (pin "4") (pinfunction "XTALIN_4") (pintype "input"))
      (node (ref "Q2") (pin "P$3") (pinfunction "2_P$3") (pintype "passive"))
    )
    (net (code "30") (name "Net-(C21-P$1)") (class "Default")
      (node (ref "C21") (pin "1") (pinfunction "P$1_1") (pintype "passive"))
      (node (ref "IC4") (pin "13") (pinfunction "USB_DM_13") (pintype "bidirectional"))
      (node (ref "R28") (pin "2") (pinfunction "P$2_2") (pintype "passive"))
    )
    (net (code "31") (name "Net-(C22-P$1)") (class "Default")
      (node (ref "C22") (pin "1") (pinfunction "P$1_1") (pintype "passive"))
      (node (ref "IC4") (pin "14") (pinfunction "USB_DP_14") (pintype "bidirectional"))
      (node (ref "R27") (pin "2") (pinfunction "P$2_2") (pintype "passive"))
      (node (ref "R29") (pin "2") (pinfunction "P$2_2") (pintype "passive"))
    )
    (net (code "32") (name "Net-(CON2-PadD+)") (class "Default")
      (node (ref "CON2") (pin "D+") (pinfunction "D+_D+") (pintype "bidirectional"))
      (node (ref "IC5") (pin "1") (pinfunction "IO1_1") (pintype "bidirectional"))
    )
    (net (code "33") (name "Net-(CON2-PadD-)") (class "Default")
      (node (ref "CON2") (pin "D-") (pinfunction "D-_D-") (pintype "bidirectional"))
      (node (ref "IC5") (pin "3") (pinfunction "IO2_3") (pintype "bidirectional"))
    )
    (net (code "34") (name "Net-(IC2-Y)") (class "Default")
      (node (ref "IC2") (pin "4") (pinfunction "Y_4") (pintype "bidirectional"))
      (node (ref "R9") (pin "2") (pinfunction "P$2_2") (pintype "passive"))
    )
    (net (code "35") (name "Net-(IC3A-PTC5)") (class "Default")
      (node (ref "IC3") (pin "77") (pinfunction "PTC5_77") (pintype "bidirectional"))
      (node (ref "R14") (pin "1") (pinfunction "P$1_1") (pintype "passive"))
    )
    (net (code "36") (name "Net-(IC3A-PTC6)") (class "Default")
      (node (ref "IC3") (pin "78") (pinfunction "PTC6_78") (pintype "bidirectional"))
      (node (ref "R15") (pin "1") (pinfunction "P$1_1") (pintype "passive"))
    )
    (net (code "37") (name "Net-(IC3B-VOUT33)") (class "Default")
      (node (ref "IC3") (pin "12") (pinfunction "VOUT33_12") (pintype "bidirectional"))
      (node (ref "IC3") (pin "13") (pinfunction "VREG_IN_13") (pintype "bidirectional"))
      (node (ref "R10") (pin "1") (pinfunction "P$1_1") (pintype "passive"))
    )
    (net (code "38") (name "Net-(IC4-PIO0_3{slash}USB_VBUS)") (class "Default")
      (node (ref "IC4") (pin "9") (pinfunction "PIO0_3/USB_VBUS_9") (pintype "bidirectional"))
      (node (ref "R19") (pin "1") (pinfunction "P$1_1") (pintype "passive"))
    )
    (net (code "39") (name "Net-(MOD1-DIG1)") (class "Default")
      (node (ref "MOD1") (pin "10") (pinfunction "DIG1_10") (pintype "bidirectional"))
      (node (ref "R17") (pin "1") (pinfunction "P$1_1") (pintype "passive"))
    )
    (net (code "40") (name "Net-(MOD1-DIG2)") (class "Default")
      (node (ref "MOD1") (pin "34") (pinfunction "DIG2_34") (pintype "bidirectional"))
      (node (ref "R16") (pin "1") (pinfunction "P$1_1") (pintype "passive"))
    )
    (net (code "41") (name "Net-(MOD1-DIG4)") (class "Default")
      (node (ref "MOD1") (pin "33") (pinfunction "DIG4_33") (pintype "bidirectional"))
      (node (ref "R18") (pin "2") (pinfunction "P$2_2") (pintype "passive"))
    )
    (net (code "42") (name "Net-(R4-P$1)") (class "Default")
      (node (ref "LED1") (pin "A") (pinfunction "A_A") (pintype "passive"))
      (node (ref "R4") (pin "1") (pinfunction "P$1_1") (pintype "passive"))
    )
    (net (code "43") (name "Net-(R5-P$1)") (class "Default")
      (node (ref "R5") (pin "1") (pinfunction "P$1_1") (pintype "passive"))
      (node (ref "R7") (pin "2") (pinfunction "P$2_2") (pintype "passive"))
      (node (ref "T1") (pin "1") (pinfunction "B_1") (pintype "passive"))
    )
    (net (code "44") (name "Net-(R11-P$2)") (class "Default")
      (node (ref "LED2") (pin "C") (pinfunction "C_C") (pintype "passive"))
      (node (ref "R11") (pin "2") (pinfunction "P$2_2") (pintype "passive"))
    )
    (net (code "45") (name "Net-(R12-P$2)") (class "Default")
      (node (ref "LED3") (pin "C") (pinfunction "C_C") (pintype "passive"))
      (node (ref "R12") (pin "2") (pinfunction "P$2_2") (pintype "passive"))
    )
    (net (code "46") (name "Net-(R13-P$2)") (class "Default")
      (node (ref "LED4") (pin "C") (pinfunction "C_C") (pintype "passive"))
      (node (ref "R13") (pin "2") (pinfunction "P$2_2") (pintype "passive"))
    )
    (net (code "47") (name "Net-(R21-P$2)") (class "Default")
      (node (ref "LED5") (pin "A") (pinfunction "A_A") (pintype "passive"))
      (node (ref "R21") (pin "2") (pinfunction "P$2_2") (pintype "passive"))
    )
    (net (code "48") (name "Net-(R22-P$2)") (class "Default")
      (node (ref "LED6") (pin "A") (pinfunction "A_A") (pintype "passive"))
      (node (ref "R22") (pin "2") (pinfunction "P$2_2") (pintype "passive"))
    )
    (net (code "49") (name "Net-(R23-P$2)") (class "Default")
      (node (ref "LED7") (pin "A") (pinfunction "A_A") (pintype "passive"))
      (node (ref "R23") (pin "2") (pinfunction "P$2_2") (pintype "passive"))
    )
    (net (code "50") (name "Net-(R24-P$2)") (class "Default")
      (node (ref "D3") (pin "K") (pinfunction "K_K") (pintype "passive"))
      (node (ref "R24") (pin "2") (pinfunction "P$2_2") (pintype "passive"))
      (node (ref "R25") (pin "2") (pinfunction "P$2_2") (pintype "passive"))
      (node (ref "SW1") (pin "P$2") (pinfunction "S_P$2") (pintype "passive"))
    )
    (net (code "51") (name "Net-(R27-P$1)") (class "Default")
      (node (ref "R27") (pin "1") (pinfunction "P$1_1") (pintype "passive"))
      (node (ref "T2") (pin "3") (pinfunction "D_3") (pintype "passive"))
    )
    (net (code "52") (name "PTA14") (class "Default")
      (node (ref "BRD1") (pin "31") (pinfunction "GPIO6_31") (pintype "bidirectional"))
      (node (ref "IC3") (pin "44") (pinfunction "PTA14_44") (pintype "bidirectional"))
    )
    (net (code "53") (name "REMAP_IO") (class "Default")
      (node (ref "IC4") (pin "20") (pinfunction "PIO0_22/AD6/CT16B1_MAT1/MISO1_20") (pintype "bidirectional"))
      (node (ref "R26") (pin "2") (pinfunction "P$2_2") (pintype "passive"))
    )
    (net (code "54") (name "RF_DIG3") (class "Default")
      (node (ref "IC3") (pin "69") (pinfunction "PTB23_69") (pintype "bidirectional"))
      (node (ref "MOD1") (pin "32") (pinfunction "DIG3_32") (pintype "bidirectional"))
    )
    (net (code "55") (name "RF_FEM_SEL") (class "Default")
      (node (ref "IC3") (pin "57") (pinfunction "PTB9_57") (pintype "bidirectional"))
      (node (ref "MOD1") (pin "38") (pinfunction "FEM_SEL_38") (pintype "bidirectional"))
    )
    (net (code "56") (name "RF_IRQ") (class "Default")
      (node (ref "IC3") (pin "76") (pinfunction "PTC4_76") (pintype "bidirectional"))
      (node (ref "MOD1") (pin "40") (pinfunction "IRQ_40") (pintype "bidirectional"))
    )
    (net (code "57") (name "RF_MISO") (class "Default")
      (node (ref "IC3") (pin "96") (pinfunction "PTD3_96") (pintype "bidirectional"))
      (node (ref "MOD1") (pin "8") (pinfunction "MISO_8") (pintype "bidirectional"))
    )
    (net (code "58") (name "RF_MOSI") (class "Default")
      (node (ref "IC3") (pin "95") (pinfunction "PTD2_95") (pintype "bidirectional"))
      (node (ref "MOD1") (pin "7") (pinfunction "MOSI_7") (pintype "bidirectional"))
    )
    (net (code "59") (name "RF_NRESET") (class "Default")
      (node (ref "IC3") (pin "97") (pinfunction "PTD4_97") (pintype "bidirectional"))
      (node (ref "MOD1") (pin "5") (pinfunction "NRESET_5") (pintype "bidirectional"))
    )
    (net (code "60") (name "RF_NSEL") (class "Default")
      (node (ref "IC3") (pin "93") (pinfunction "PTD0_93") (pintype "bidirectional"))
      (node (ref "MOD1") (pin "6") (pinfunction "NSEL_6") (pintype "bidirectional"))
    )
    (net (code "61") (name "RF_SCL") (class "Default")
      (node (ref "IC3") (pin "31") (pinfunction "PTE24_31") (pintype "bidirectional"))
      (node (ref "MOD1") (pin "36") (pinfunction "MAC_SCL_36") (pintype "bidirectional"))
    )
    (net (code "62") (name "RF_SCLK") (class "Default")
      (node (ref "IC3") (pin "94") (pinfunction "PTD1_94") (pintype "bidirectional"))
      (node (ref "MOD1") (pin "9") (pinfunction "SCLK_9") (pintype "bidirectional"))
    )
    (net (code "63") (name "RF_SDA") (class "Default")
      (node (ref "IC3") (pin "32") (pinfunction "PTE25_32") (pintype "bidirectional"))
      (node (ref "MOD1") (pin "37") (pinfunction "MAC_SDA_37") (pintype "bidirectional"))
    )
    (net (code "64") (name "RF_SLP_TR") (class "Default")
      (node (ref "IC3") (pin "73") (pinfunction "PTC3_73") (pintype "bidirectional"))
      (node (ref "MOD1") (pin "35") (pinfunction "SLP_TR_35") (pintype "bidirectional"))
    )
    (net (code "65") (name "RPI_ID_SCL") (class "Default")
      (node (ref "BRD1") (pin "28") (pinfunction "ID_SC_28") (pintype "bidirectional"))
      (node (ref "IC1") (pin "6") (pinfunction "SCL_6") (pintype "input"))
      (node (ref "R2") (pin "1") (pinfunction "P$1_1") (pintype "passive"))
    )
    (net (code "66") (name "RPI_ID_SDA") (class "Default")
      (node (ref "BRD1") (pin "27") (pinfunction "ID_SD_27") (pintype "bidirectional"))
      (node (ref "IC1") (pin "5") (pinfunction "SDA_5") (pintype "bidirectional"))
      (node (ref "R1") (pin "1") (pinfunction "P$1_1") (pintype "passive"))
    )
    (net (code "67") (name "RPI_ID_WP") (class "Default")
      (node (ref "IC1") (pin "7") (pinfunction "WP_7") (pintype "input"))
      (node (ref "R3") (pin "1") (pinfunction "P$1_1") (pintype "passive"))
      (node (ref "TP16") (pin "TP") (pinfunction "TP_TP") (pintype "input"))
    )
    (net (code "68") (name "RPI_K64F_RESET") (class "Default")
      (node (ref "BRD1") (pin "40") (pinfunction "GPIO21_40") (pintype "bidirectional"))
      (node (ref "R5") (pin "2") (pinfunction "P$2_2") (pintype "passive"))
      (node (ref "RESET-EN") (pin "1") (pinfunction "1_1") (pintype "passive"))
    )
    (net (code "69") (name "RPI_SCL") (class "Default")
      (node (ref "BRD1") (pin "5") (pinfunction "GPIO3_5") (pintype "bidirectional"))
      (node (ref "IC3") (pin "42") (pinfunction "PTA12_42") (pintype "bidirectional"))
    )
    (net (code "70") (name "RPI_SDA") (class "Default")
      (node (ref "BRD1") (pin "3") (pinfunction "GPIO2_3") (pintype "bidirectional"))
      (node (ref "IC3") (pin "43") (pinfunction "PTA13_43") (pintype "bidirectional"))
    )
    (net (code "71") (name "TGT_NRESET") (class "Default")
      (node (ref "CON1") (pin "3") (pinfunction "NRESET_3") (pintype "passive"))
      (node (ref "D3") (pin "A") (pinfunction "A_A") (pintype "passive"))
      (node (ref "IC3") (pin "52") (pinfunction "NRESET_52") (pintype "bidirectional"))
      (node (ref "R9") (pin "1") (pinfunction "P$1_1") (pintype "passive"))
    )
    (net (code "72") (name "TGT_NRESET_DAPLINK") (class "Default")
      (node (ref "IC2") (pin "1") (pinfunction "B_1") (pintype "bidirectional"))
      (node (ref "IC4") (pin "8") (pinfunction "PIO0_2/SSEL0/CT16B0_CAP0_8") (pintype "bidirectional"))
      (node (ref "R6") (pin "2") (pinfunction "P$2_2") (pintype "passive"))
    )
    (net (code "73") (name "TGT_NRESET_FB") (class "Default")
      (node (ref "IC4") (pin "1") (pinfunction "PIO1_19/~{DTR}/SSEL1_1") (pintype "bidirectional"))
      (node (ref "R24") (pin "1") (pinfunction "P$1_1") (pintype "passive"))
    )
    (net (code "74") (name "TGT_NRESET_FB_ISP") (class "Default")
      (node (ref "IC4") (pin "3") (pinfunction "PIO0_1/CLKOUT/CT32B0_MAT2/USB_FTOGGLE_3") (pintype "bidirectional"))
      (node (ref "R25") (pin "1") (pinfunction "P$1_1") (pintype "passive"))
    )
    (net (code "75") (name "TGT_NRESET_RPI") (class "Default")
      (node (ref "C4") (pin "1") (pinfunction "P$1_1") (pintype "passive"))
      (node (ref "IC2") (pin "2") (pinfunction "A_2") (pintype "bidirectional"))
      (node (ref "R8") (pin "1") (pinfunction "P$1_1") (pintype "passive"))
      (node (ref "T1") (pin "3") (pinfunction "C_3") (pintype "passive"))
    )
    (net (code "76") (name "TGT_SWCLK") (class "Default")
      (node (ref "BRD1") (pin "23") (pinfunction "GPIO11_23") (pintype "bidirectional"))
      (node (ref "CON1") (pin "4") (pinfunction "SWCLK/TCLK_4") (pintype "passive"))
      (node (ref "IC3") (pin "34") (pinfunction "SWCLK_34") (pintype "bidirectional"))
      (node (ref "IC4") (pin "18") (pinfunction "PIO0_9/MOSI0/CT16B0_MAT1_18") (pintype "bidirectional"))
    )
    (net (code "77") (name "TGT_SWDIO") (class "Default")
      (node (ref "CON1") (pin "2") (pinfunction "SWDIO/TMS_2") (pintype "passive"))
      (node (ref "IC3") (pin "37") (pinfunction "SWDIO_37") (pintype "bidirectional"))
      (node (ref "IC4") (pin "17") (pinfunction "PIO0_8/MISO0/CT16B0_MAT0_17") (pintype "bidirectional"))
    )
    (net (code "78") (name "USB-DM") (class "Default")
      (node (ref "IC5") (pin "4") (pinfunction "IO2_4") (pintype "bidirectional"))
      (node (ref "R28") (pin "1") (pinfunction "P$1_1") (pintype "passive"))
    )
    (net (code "79") (name "USB-DP") (class "Default")
      (node (ref "IC5") (pin "6") (pinfunction "IO1_6") (pintype "bidirectional"))
      (node (ref "R29") (pin "1") (pinfunction "P$1_1") (pintype "passive"))
    )
    (net (code "80") (name "USB-SCON") (class "Default")
      (node (ref "IC4") (pin "15") (pinfunction "PIO0_6/~{USB_CONNECT}/SCK0_15") (pintype "bidirectional"))
      (node (ref "T2") (pin "1") (pinfunction "G_1") (pintype "passive"))
    )
    (net (code "81") (name "VBUS_IF") (class "Default")
      (node (ref "CON2") (pin "VBUS") (pinfunction "VBUS_VBUS") (pintype "bidirectional"))
      (node (ref "IC5") (pin "5") (pinfunction "VBUS_5") (pintype "bidirectional"))
      (node (ref "IC6") (pin "3") (pinfunction "IN_3") (pintype "input"))
    )
    (net (code "82") (name "unconnected-(BRD1-5V-Pad2)") (class "Default")
      (node (ref "BRD1") (pin "2") (pinfunction "5V_2") (pintype "bidirectional"))
    )
    (net (code "83") (name "unconnected-(BRD1-5V-Pad4)") (class "Default")
      (node (ref "BRD1") (pin "4") (pinfunction "5V_4") (pintype "bidirectional"))
    )
    (net (code "84") (name "unconnected-(BRD1-GPIO4-Pad7)") (class "Default")
      (node (ref "BRD1") (pin "7") (pinfunction "GPIO4_7") (pintype "bidirectional"))
    )
    (net (code "85") (name "unconnected-(BRD1-GPIO5-Pad29)") (class "Default")
      (node (ref "BRD1") (pin "29") (pinfunction "GPIO5_29") (pintype "bidirectional"))
    )
    (net (code "86") (name "unconnected-(BRD1-GPIO7-Pad26)") (class "Default")
      (node (ref "BRD1") (pin "26") (pinfunction "GPIO7_26") (pintype "bidirectional"))
    )
    (net (code "87") (name "unconnected-(BRD1-GPIO12-Pad32)") (class "Default")
      (node (ref "BRD1") (pin "32") (pinfunction "GPIO12_32") (pintype "bidirectional"))
    )
    (net (code "88") (name "unconnected-(BRD1-GPIO13-Pad33)") (class "Default")
      (node (ref "BRD1") (pin "33") (pinfunction "GPIO13_33") (pintype "bidirectional"))
    )
    (net (code "89") (name "unconnected-(BRD1-GPIO18-Pad12)") (class "Default")
      (node (ref "BRD1") (pin "12") (pinfunction "GPIO18_12") (pintype "bidirectional"))
    )
    (net (code "90") (name "unconnected-(BRD1-GPIO19-Pad35)") (class "Default")
      (node (ref "BRD1") (pin "35") (pinfunction "GPIO19_35") (pintype "bidirectional"))
    )
    (net (code "91") (name "unconnected-(BRD1-GPIO20-Pad38)") (class "Default")
      (node (ref "BRD1") (pin "38") (pinfunction "GPIO20_38") (pintype "bidirectional"))
    )
    (net (code "92") (name "unconnected-(BRD1-GPIO22-Pad15)") (class "Default")
      (node (ref "BRD1") (pin "15") (pinfunction "GPIO22_15") (pintype "bidirectional"))
    )
    (net (code "93") (name "unconnected-(BRD1-GPIO23-Pad16)") (class "Default")
      (node (ref "BRD1") (pin "16") (pinfunction "GPIO23_16") (pintype "bidirectional"))
    )
    (net (code "94") (name "unconnected-(BRD1-GPIO24-Pad18)") (class "Default")
      (node (ref "BRD1") (pin "18") (pinfunction "GPIO24_18") (pintype "bidirectional"))
    )
    (net (code "95") (name "unconnected-(BRD1-GPIO25-Pad22)") (class "Default")
      (node (ref "BRD1") (pin "22") (pinfunction "GPIO25_22") (pintype "bidirectional"))
    )
    (net (code "96") (name "unconnected-(BRD1-GPIO26-Pad37)") (class "Default")
      (node (ref "BRD1") (pin "37") (pinfunction "GPIO26_37") (pintype "bidirectional"))
    )
    (net (code "97") (name "unconnected-(BRD1-GPIO27-Pad13)") (class "Default")
      (node (ref "BRD1") (pin "13") (pinfunction "GPIO27_13") (pintype "bidirectional"))
    )
    (net (code "98") (name "unconnected-(CON1-SWO{slash}TDO-Pad6)") (class "Default")
      (node (ref "CON1") (pin "6") (pinfunction "SWO/TDO_6") (pintype "passive"))
    )
    (net (code "99") (name "unconnected-(IC3A-ADC0_DM0-Pad19)") (class "Default")
      (node (ref "IC3") (pin "19") (pinfunction "ADC0_DM0_19") (pintype "bidirectional"))
    )
    (net (code "100") (name "unconnected-(IC3A-ADC0_DM1-Pad15)") (class "Default")
      (node (ref "IC3") (pin "15") (pinfunction "ADC0_DM1_15") (pintype "bidirectional"))
    )
    (net (code "101") (name "unconnected-(IC3A-ADC0_DP0-Pad18)") (class "Default")
      (node (ref "IC3") (pin "18") (pinfunction "ADC0_DP0_18") (pintype "bidirectional"))
    )
    (net (code "102") (name "unconnected-(IC3A-ADC0_DP1-Pad14)") (class "Default")
      (node (ref "IC3") (pin "14") (pinfunction "ADC0_DP1_14") (pintype "bidirectional"))
    )
    (net (code "103") (name "unconnected-(IC3A-ADC1_DM0-Pad21)") (class "Default")
      (node (ref "IC3") (pin "21") (pinfunction "ADC1_DM0_21") (pintype "bidirectional"))
    )
    (net (code "104") (name "unconnected-(IC3A-ADC1_DM1-Pad17)") (class "Default")
      (node (ref "IC3") (pin "17") (pinfunction "ADC1_DM1_17") (pintype "bidirectional"))
    )
    (net (code "105") (name "unconnected-(IC3A-ADC1_DP0-Pad20)") (class "Default")
      (node (ref "IC3") (pin "20") (pinfunction "ADC1_DP0_20") (pintype "bidirectional"))
    )
    (net (code "106") (name "unconnected-(IC3A-ADC1_DP1-Pad16)") (class "Default")
      (node (ref "IC3") (pin "16") (pinfunction "ADC1_DP1_16") (pintype "bidirectional"))
    )
    (net (code "107") (name "unconnected-(IC3A-PTA5-Pad39)") (class "Default")
      (node (ref "IC3") (pin "39") (pinfunction "PTA5_39") (pintype "bidirectional"))
    )
    (net (code "108") (name "unconnected-(IC3A-PTA15-Pad45)") (class "Default")
      (node (ref "IC3") (pin "45") (pinfunction "PTA15_45") (pintype "bidirectional"))
    )
    (net (code "109") (name "unconnected-(IC3A-PTA16-Pad46)") (class "Default")
      (node (ref "IC3") (pin "46") (pinfunction "PTA16_46") (pintype "bidirectional"))
    )
    (net (code "110") (name "unconnected-(IC3A-PTA17-Pad47)") (class "Default")
      (node (ref "IC3") (pin "47") (pinfunction "PTA17_47") (pintype "bidirectional"))
    )
    (net (code "111") (name "unconnected-(IC3A-PTB0-Pad53)") (class "Default")
      (node (ref "IC3") (pin "53") (pinfunction "PTB0_53") (pintype "bidirectional"))
    )
    (net (code "112") (name "unconnected-(IC3A-PTB1-Pad54)") (class "Default")
      (node (ref "IC3") (pin "54") (pinfunction "PTB1_54") (pintype "bidirectional"))
    )
    (net (code "113") (name "unconnected-(IC3A-PTB10-Pad58)") (class "Default")
      (node (ref "IC3") (pin "58") (pinfunction "PTB10_58") (pintype "bidirectional"))
    )
    (net (code "114") (name "unconnected-(IC3A-PTB11-Pad59)") (class "Default")
      (node (ref "IC3") (pin "59") (pinfunction "PTB11_59") (pintype "bidirectional"))
    )
    (net (code "115") (name "unconnected-(IC3A-PTB18-Pad64)") (class "Default")
      (node (ref "IC3") (pin "64") (pinfunction "PTB18_64") (pintype "bidirectional"))
    )
    (net (code "116") (name "unconnected-(IC3A-PTB19-Pad65)") (class "Default")
      (node (ref "IC3") (pin "65") (pinfunction "PTB19_65") (pintype "bidirectional"))
    )
    (net (code "117") (name "unconnected-(IC3A-PTB20-Pad66)") (class "Default")
      (node (ref "IC3") (pin "66") (pinfunction "PTB20_66") (pintype "bidirectional"))
    )
    (net (code "118") (name "unconnected-(IC3A-PTC0-Pad70)") (class "Default")
      (node (ref "IC3") (pin "70") (pinfunction "PTC0_70") (pintype "bidirectional"))
    )
    (net (code "119") (name "unconnected-(IC3A-PTC1-Pad71)") (class "Default")
      (node (ref "IC3") (pin "71") (pinfunction "PTC1_71") (pintype "bidirectional"))
    )
    (net (code "120") (name "unconnected-(IC3A-PTC2-Pad72)") (class "Default")
      (node (ref "IC3") (pin "72") (pinfunction "PTC2_72") (pintype "bidirectional"))
    )
    (net (code "121") (name "unconnected-(IC3A-PTC7-Pad79)") (class "Default")
      (node (ref "IC3") (pin "79") (pinfunction "PTC7_79") (pintype "bidirectional"))
    )
    (net (code "122") (name "unconnected-(IC3A-PTC8-Pad80)") (class "Default")
      (node (ref "IC3") (pin "80") (pinfunction "PTC8_80") (pintype "bidirectional"))
    )
    (net (code "123") (name "unconnected-(IC3A-PTC9-Pad81)") (class "Default")
      (node (ref "IC3") (pin "81") (pinfunction "PTC9_81") (pintype "bidirectional"))
    )
    (net (code "124") (name "unconnected-(IC3A-PTC10-Pad82)") (class "Default")
      (node (ref "IC3") (pin "82") (pinfunction "PTC10_82") (pintype "bidirectional"))
    )
    (net (code "125") (name "unconnected-(IC3A-PTC11-Pad83)") (class "Default")
      (node (ref "IC3") (pin "83") (pinfunction "PTC11_83") (pintype "bidirectional"))
    )
    (net (code "126") (name "unconnected-(IC3A-PTC12-Pad84)") (class "Default")
      (node (ref "IC3") (pin "84") (pinfunction "PTC12_84") (pintype "bidirectional"))
    )
    (net (code "127") (name "unconnected-(IC3A-PTC13-Pad85)") (class "Default")
      (node (ref "IC3") (pin "85") (pinfunction "PTC13_85") (pintype "bidirectional"))
    )
    (net (code "128") (name "unconnected-(IC3A-PTC14-Pad86)") (class "Default")
      (node (ref "IC3") (pin "86") (pinfunction "PTC14_86") (pintype "bidirectional"))
    )
    (net (code "129") (name "unconnected-(IC3A-PTC15-Pad87)") (class "Default")
      (node (ref "IC3") (pin "87") (pinfunction "PTC15_87") (pintype "bidirectional"))
    )
    (net (code "130") (name "unconnected-(IC3A-PTC16-Pad90)") (class "Default")
      (node (ref "IC3") (pin "90") (pinfunction "PTC16_90") (pintype "bidirectional"))
    )
    (net (code "131") (name "unconnected-(IC3A-PTC17-Pad91)") (class "Default")
      (node (ref "IC3") (pin "91") (pinfunction "PTC17_91") (pintype "bidirectional"))
    )
    (net (code "132") (name "unconnected-(IC3A-PTC18-Pad92)") (class "Default")
      (node (ref "IC3") (pin "92") (pinfunction "PTC18_92") (pintype "bidirectional"))
    )
    (net (code "133") (name "unconnected-(IC3A-PTD5-Pad98)") (class "Default")
      (node (ref "IC3") (pin "98") (pinfunction "PTD5_98") (pintype "bidirectional"))
    )
    (net (code "134") (name "unconnected-(IC3A-PTD6-Pad99)") (class "Default")
      (node (ref "IC3") (pin "99") (pinfunction "PTD6_99") (pintype "bidirectional"))
    )
    (net (code "135") (name "unconnected-(IC3A-PTD7-Pad100)") (class "Default")
      (node (ref "IC3") (pin "100") (pinfunction "PTD7_100") (pintype "bidirectional"))
    )
    (net (code "136") (name "unconnected-(IC3A-PTE4-Pad5)") (class "Default")
      (node (ref "IC3") (pin "5") (pinfunction "PTE4_5") (pintype "bidirectional"))
    )
    (net (code "137") (name "unconnected-(IC3A-PTE5-Pad6)") (class "Default")
      (node (ref "IC3") (pin "6") (pinfunction "PTE5_6") (pintype "bidirectional"))
    )
    (net (code "138") (name "unconnected-(IC3A-PTE6-Pad7)") (class "Default")
      (node (ref "IC3") (pin "7") (pinfunction "PTE6_7") (pintype "bidirectional"))
    )
    (net (code "139") (name "unconnected-(IC3A-USB0_DM-Pad11)") (class "Default")
      (node (ref "IC3") (pin "11") (pinfunction "USB0_DM_11") (pintype "bidirectional"))
    )
    (net (code "140") (name "unconnected-(IC3A-USB0_DP-Pad10)") (class "Default")
      (node (ref "IC3") (pin "10") (pinfunction "USB0_DP_10") (pintype "bidirectional"))
    )
    (net (code "141") (name "unconnected-(IC3B-DAC0_OUT-Pad27)") (class "Default")
      (node (ref "IC3") (pin "27") (pinfunction "DAC0_OUT_27") (pintype "bidirectional"))
    )
    (net (code "142") (name "unconnected-(IC3B-VREF_OUT-Pad26)") (class "Default")
      (node (ref "IC3") (pin "26") (pinfunction "VREF_OUT_26") (pintype "bidirectional"))
    )
    (net (code "143") (name "unconnected-(IC3B-XTAL0-Pad51)") (class "Default")
      (node (ref "IC3") (pin "51") (pinfunction "XTAL0_51") (pintype "bidirectional"))
    )
    (net (code "144") (name "unconnected-(IC4-PIO0_4{slash}SCL-Pad10)") (class "Default")
      (node (ref "IC4") (pin "10") (pinfunction "PIO0_4/SCL_10") (pintype "bidirectional"))
    )
    (net (code "145") (name "unconnected-(IC4-PIO0_5{slash}SDA-Pad11)") (class "Default")
      (node (ref "IC4") (pin "11") (pinfunction "PIO0_5/SDA_11") (pintype "bidirectional"))
    )
    (net (code "146") (name "unconnected-(IC4-PIO0_16{slash}AD5{slash}CT32B1_MAT3{slash}WAKEUP-Pad26)") (class "Default")
      (node (ref "IC4") (pin "26") (pinfunction "PIO0_16/AD5/CT32B1_MAT3/WAKEUP_26") (pintype "bidirectional"))
    )
    (net (code "147") (name "unconnected-(IC4-PIO0_23{slash}AD7-Pad27)") (class "Default")
      (node (ref "IC4") (pin "27") (pinfunction "PIO0_23/AD7_27") (pintype "bidirectional"))
    )
    (net (code "148") (name "unconnected-(IC4-PIO1_15{slash}~{DCD}{slash}CT16B0_MAT2{slash}SCK1-Pad28)") (class "Default")
      (node (ref "IC4") (pin "28") (pinfunction "PIO1_15/~{DCD}/CT16B0_MAT2/SCK1_28") (pintype "bidirectional"))
    )
    (net (code "149") (name "unconnected-(IC4-SWCLK{slash}PIO0_10{slash}SCK0{slash}CT16B0_MAT2-Pad19)") (class "Default")
      (node (ref "IC4") (pin "19") (pinfunction "SWCLK/PIO0_10/SCK0/CT16B0_MAT2_19") (pintype "bidirectional"))
    )
    (net (code "150") (name "unconnected-(IC4-SWDIO{slash}PIO0_15{slash}AD4{slash}CT32B1_MAT2-Pad25)") (class "Default")
      (node (ref "IC4") (pin "25") (pinfunction "SWDIO/PIO0_15/AD4/CT32B1_MAT2_25") (pintype "bidirectional"))
    )
    (net (code "151") (name "unconnected-(IC4-TDO{slash}PIO0_13{slash}AD2{slash}CT32B1_MAT0-Pad23)") (class "Default")
      (node (ref "IC4") (pin "23") (pinfunction "TDO/PIO0_13/AD2/CT32B1_MAT0_23") (pintype "bidirectional"))
    )
    (net (code "152") (name "unconnected-(IC4-TMS{slash}PIO0_12{slash}AD1{slash}CT32B1_CAP0-Pad22)") (class "Default")
      (node (ref "IC4") (pin "22") (pinfunction "TMS/PIO0_12/AD1/CT32B1_CAP0_22") (pintype "bidirectional"))
    )
    (net (code "153") (name "unconnected-(IC4-~{TRST}{slash}PIO0_14{slash}AD3{slash}CT32B1_MAT1-Pad24)") (class "Default")
      (node (ref "IC4") (pin "24") (pinfunction "~{TRST}/PIO0_14/AD3/CT32B1_MAT1_24") (pintype "bidirectional"))
    )
    (net (code "154") (name "unconnected-(MOD1-CLKM-Pad39)") (class "Default")
      (node (ref "MOD1") (pin "39") (pinfunction "CLKM_39") (pintype "bidirectional"))
    )
  )
)
